# medibox.net
KiCad netlist of a schematic drawn in Altium Designer
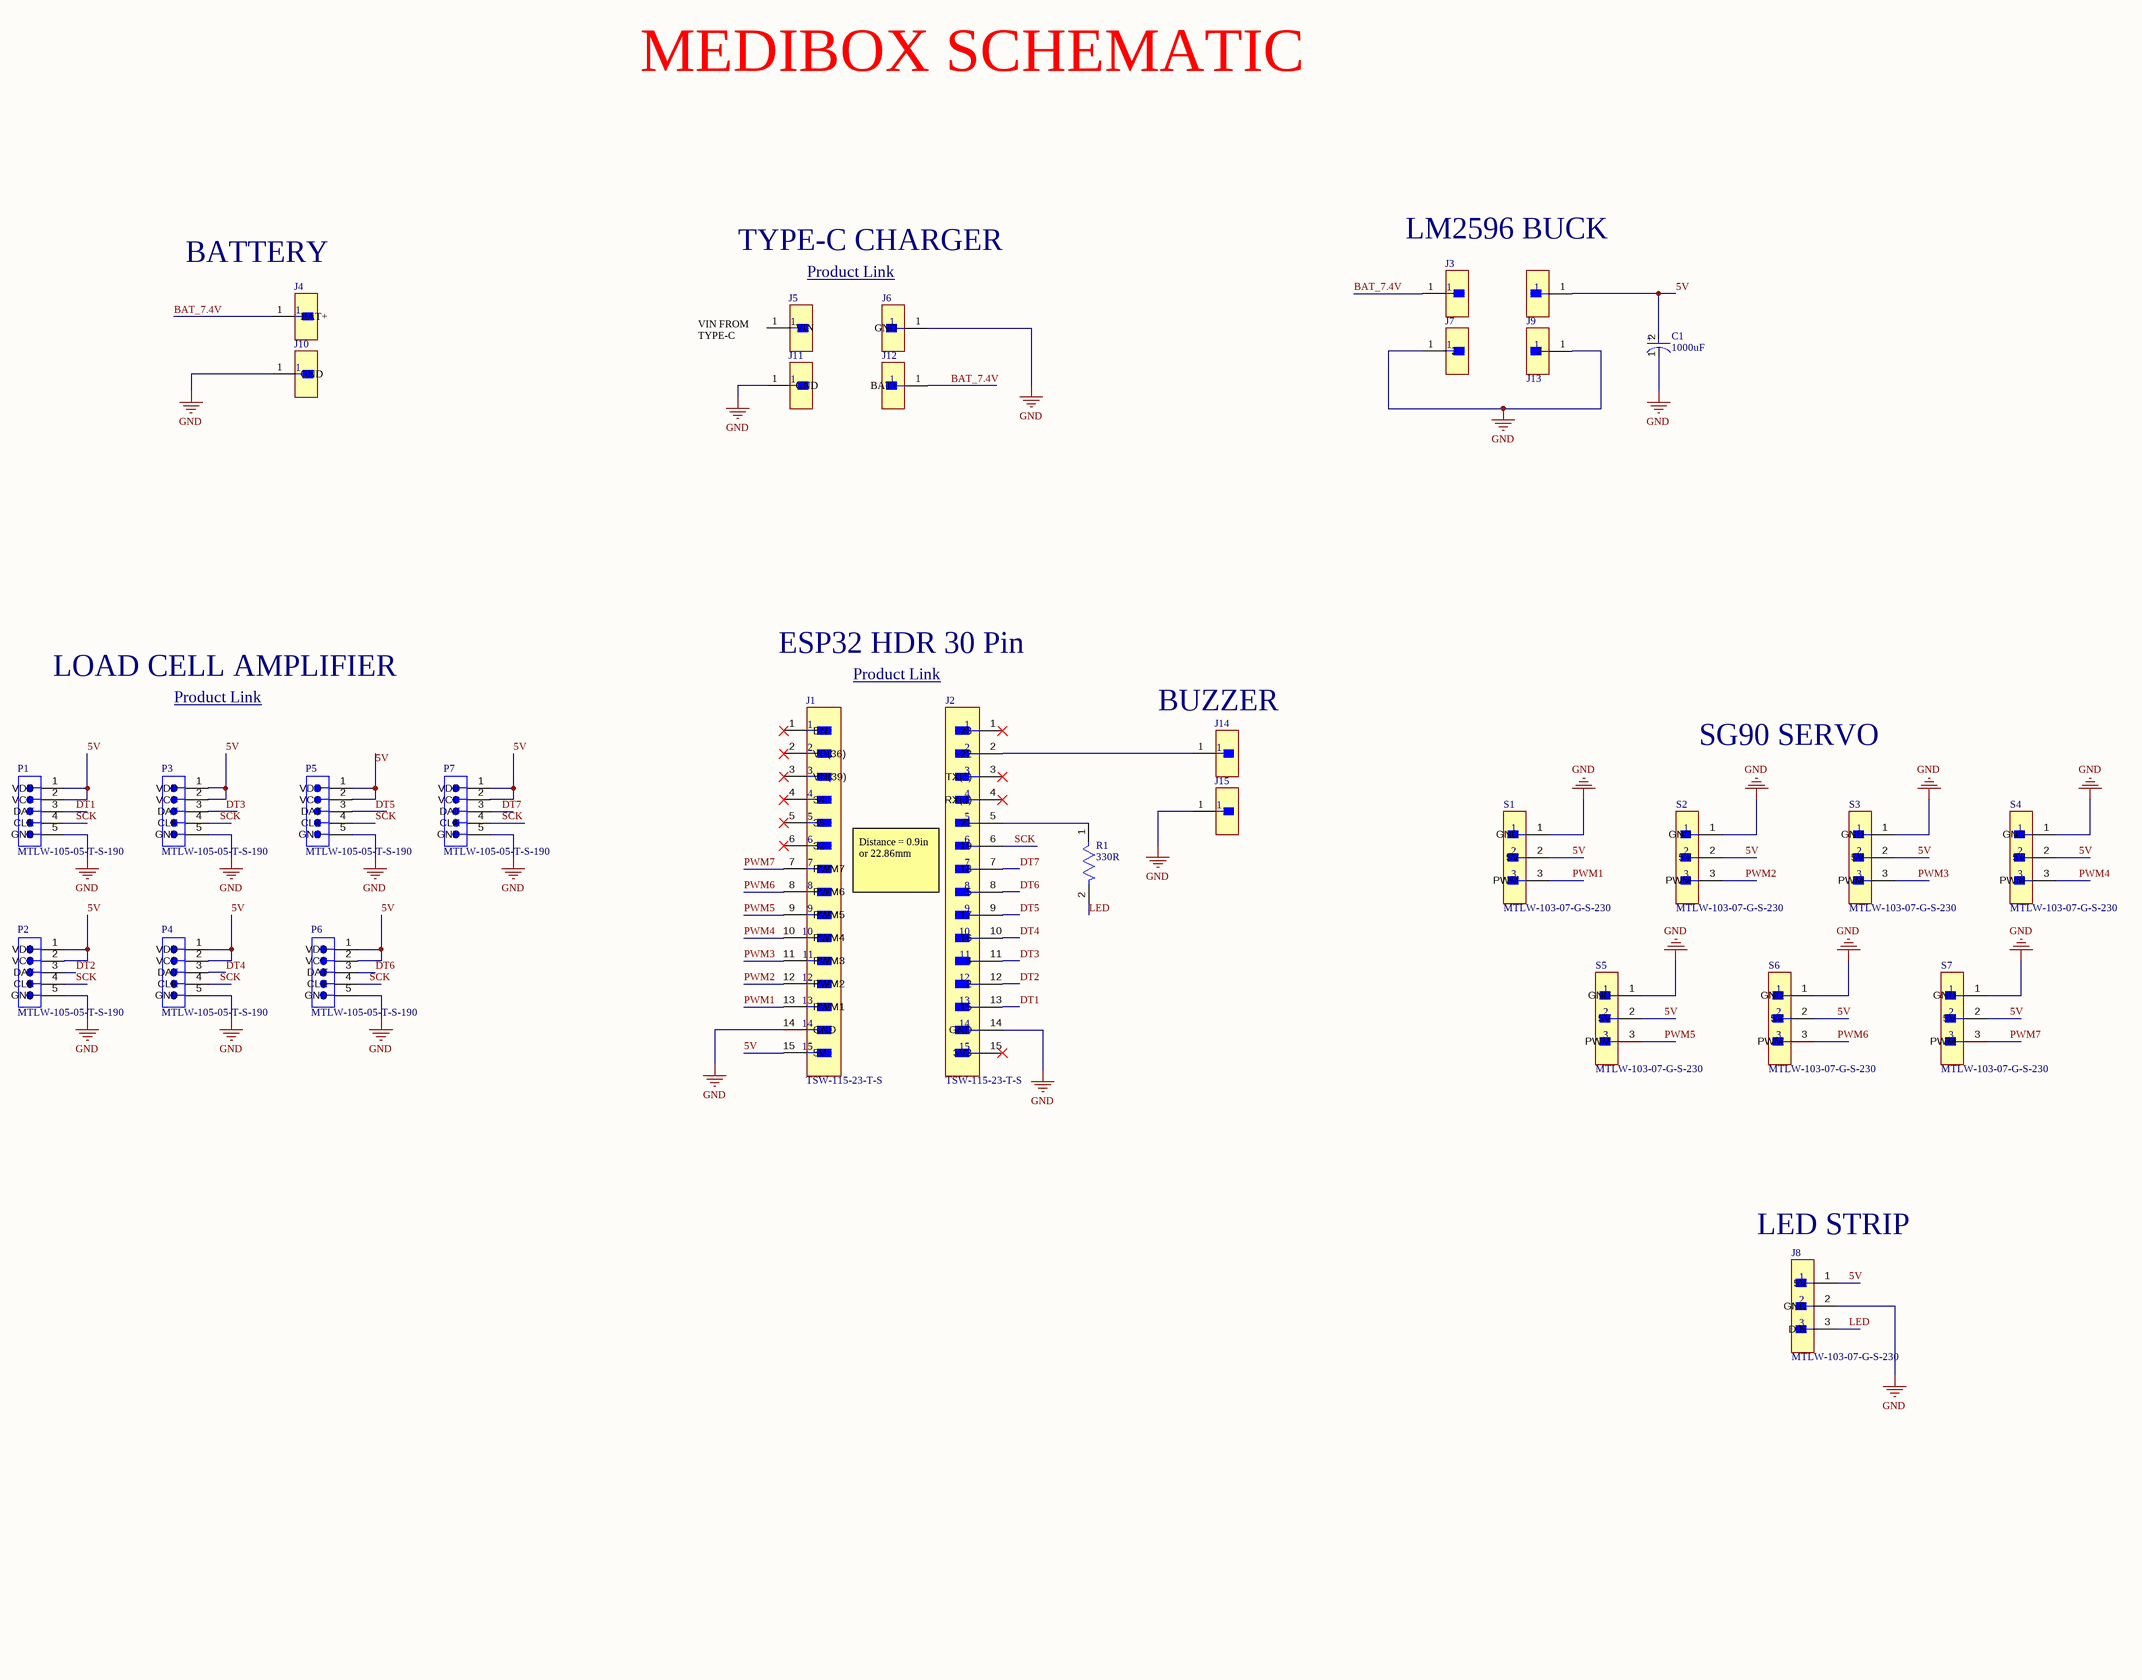
[diagram p0: medibox.SchDoc]

(export (version "E")
  (design (tool "Eeschema 10.0.6"))
  (components
    (comp (ref "C1")
      (value "1000uF")
      (footprint "FP-RAD-TH-D_10_0_5-L_25_2-MFG")
      (description "EEUFC1C102B Aluminum Electrolytic Capacitors (Radial Lead Type) AEC-Q200 Qualified 1000uF ±20% 16V")
      (fields (field (name "TOLERANCE") "20%"))
      (libsource (lib "Altium Content Vault") (part "a00bbbee19879c290e62620ae7e47b1"))
    )
    (comp (ref "J1")
      (value "TSW-115-23-T-S")
      (footprint "FP-TSW-115-23-T-S-MFG")
      (description "CONN HEADER VERT 15POS 2.54MM")
      (libsource (lib "Altium Content Vault") (part "9e54aee09c46527fb07af492d4d8164"))
    )
    (comp (ref "J2")
      (value "TSW-115-23-T-S")
      (footprint "FP-TSW-115-23-T-S-MFG")
      (description "CONN HEADER VERT 15POS 2.54MM")
      (libsource (lib "") (part "9e54aee09c46527fb07af492d4d8164_1"))
    )
    (comp (ref "J3")
      (value "68000-401HLF")
      (footprint "FP-68000-401HLF-MFG")
      (description "68000-401HLF Conn Unshrouded Header HDR 1 POS Solder ST Top Entry Thru-Hole BergStik® Bulk")
      (libsource (lib "") (part "dd45045ce8184df9e99e12baf3f412c_2"))
    )
    (comp (ref "J4")
      (value "68000-401HLF")
      (footprint "FP-68000-401HLF-MFG")
      (description "68000-401HLF Conn Unshrouded Header HDR 1 POS Solder ST Top Entry Thru-Hole BergStik® Bulk")
      (libsource (lib "") (part "dd45045ce8184df9e99e12baf3f412c_3"))
    )
    (comp (ref "J5")
      (value "68000-401HLF")
      (footprint "FP-68000-401HLF-MFG")
      (description "68000-401HLF Conn Unshrouded Header HDR 1 POS Solder ST Top Entry Thru-Hole BergStik® Bulk")
      (libsource (lib "") (part "dd45045ce8184df9e99e12baf3f412c_6"))
    )
    (comp (ref "J6")
      (value "68000-401HLF")
      (footprint "FP-68000-401HLF-MFG")
      (description "68000-401HLF Conn Unshrouded Header HDR 1 POS Solder ST Top Entry Thru-Hole BergStik® Bulk")
      (libsource (lib "") (part "dd45045ce8184df9e99e12baf3f412c_1"))
    )
    (comp (ref "J7")
      (value "68000-401HLF")
      (footprint "FP-68000-401HLF-MFG")
      (description "68000-401HLF Conn Unshrouded Header HDR 1 POS Solder ST Top Entry Thru-Hole BergStik® Bulk")
      (libsource (lib "") (part "dd45045ce8184df9e99e12baf3f412c_5"))
    )
    (comp (ref "J8")
      (value "MTLW-103-07-G-S-230")
      (footprint "FP-MTLW-103-07-G-S-230-MFG")
      (description "CONN HEADER VERT 3POS 2.54MM")
      (libsource (lib "Altium Content Vault") (part "0d3f023dd272f625e17a2be33dea85f"))
    )
    (comp (ref "J9")
      (value "68000-401HLF")
      (footprint "FP-68000-401HLF-MFG")
      (description "68000-401HLF Conn Unshrouded Header HDR 1 POS Solder ST Top Entry Thru-Hole BergStik® Bulk")
      (libsource (lib "") (part "dd45045ce8184df9e99e12baf3f412c_7"))
    )
    (comp (ref "J10")
      (value "68000-401HLF")
      (footprint "FP-68000-401HLF-MFG")
      (description "68000-401HLF Conn Unshrouded Header HDR 1 POS Solder ST Top Entry Thru-Hole BergStik® Bulk")
      (libsource (lib "Altium Content Vault") (part "dd45045ce8184df9e99e12baf3f412c"))
    )
    (comp (ref "J11")
      (value "68000-401HLF")
      (footprint "FP-68000-401HLF-MFG")
      (description "68000-401HLF Conn Unshrouded Header HDR 1 POS Solder ST Top Entry Thru-Hole BergStik® Bulk")
      (libsource (lib "Altium Content Vault") (part "dd45045ce8184df9e99e12baf3f412c"))
    )
    (comp (ref "J12")
      (value "68000-401HLF")
      (footprint "FP-68000-401HLF-MFG")
      (description "68000-401HLF Conn Unshrouded Header HDR 1 POS Solder ST Top Entry Thru-Hole BergStik® Bulk")
      (libsource (lib "") (part "dd45045ce8184df9e99e12baf3f412c_1"))
    )
    (comp (ref "J13")
      (value "68000-401HLF")
      (footprint "FP-68000-401HLF-MFG")
      (description "68000-401HLF Conn Unshrouded Header HDR 1 POS Solder ST Top Entry Thru-Hole BergStik® Bulk")
      (libsource (lib "") (part "dd45045ce8184df9e99e12baf3f412c_1"))
    )
    (comp (ref "J14")
      (value "68000-401HLF")
      (footprint "FP-68000-401HLF-MFG")
      (description "68000-401HLF Conn Unshrouded Header HDR 1 POS Solder ST Top Entry Thru-Hole BergStik® Bulk")
      (libsource (lib "") (part "dd45045ce8184df9e99e12baf3f412c_2"))
    )
    (comp (ref "J15")
      (value "68000-401HLF")
      (footprint "FP-68000-401HLF-MFG")
      (description "68000-401HLF Conn Unshrouded Header HDR 1 POS Solder ST Top Entry Thru-Hole BergStik® Bulk")
      (libsource (lib "") (part "dd45045ce8184df9e99e12baf3f412c_4"))
    )
    (comp (ref "P1")
      (value "MTLW-105-05-T-S-190")
      (footprint "SMTC-MTLW-105-05-X-S-190")
      (fields (field (name "MANUFACTURER") "Samtec"))
      (libsource (lib "Altium Content Vault") (part "SMTC-MTLW-105-05-X-S-190"))
    )
    (comp (ref "P2")
      (value "MTLW-105-05-T-S-190")
      (footprint "SMTC-MTLW-105-05-X-S-190")
      (fields (field (name "MANUFACTURER") "Samtec"))
      (libsource (lib "Altium Content Vault") (part "SMTC-MTLW-105-05-X-S-190"))
    )
    (comp (ref "P3")
      (value "MTLW-105-05-T-S-190")
      (footprint "SMTC-MTLW-105-05-X-S-190")
      (fields (field (name "MANUFACTURER") "Samtec"))
      (libsource (lib "Altium Content Vault") (part "SMTC-MTLW-105-05-X-S-190"))
    )
    (comp (ref "P4")
      (value "MTLW-105-05-T-S-190")
      (footprint "SMTC-MTLW-105-05-X-S-190")
      (fields (field (name "MANUFACTURER") "Samtec"))
      (libsource (lib "Altium Content Vault") (part "SMTC-MTLW-105-05-X-S-190"))
    )
    (comp (ref "P5")
      (value "MTLW-105-05-T-S-190")
      (footprint "SMTC-MTLW-105-05-X-S-190")
      (fields (field (name "MANUFACTURER") "Samtec"))
      (libsource (lib "Altium Content Vault") (part "SMTC-MTLW-105-05-X-S-190"))
    )
    (comp (ref "P6")
      (value "MTLW-105-05-T-S-190")
      (footprint "SMTC-MTLW-105-05-X-S-190")
      (fields (field (name "MANUFACTURER") "Samtec"))
      (libsource (lib "Altium Content Vault") (part "SMTC-MTLW-105-05-X-S-190"))
    )
    (comp (ref "P7")
      (value "MTLW-105-05-T-S-190")
      (footprint "SMTC-MTLW-105-05-X-S-190")
      (fields (field (name "MANUFACTURER") "Samtec"))
      (libsource (lib "Altium Content Vault") (part "SMTC-MTLW-105-05-X-S-190"))
    )
    (comp (ref "R1")
      (value "330R")
      (footprint "FP-RMCF0805-IPC_C")
      (description "RMCF0805FT330R 330Ω ±1% 0.125W 0805 Thick Film Chip Resistor AEC-Q200 compliant")
      (fields (field (name "TOLERANCE") "1%"))
      (libsource (lib "Altium Content Vault") (part "1029c3af85768c4190bb7ad29bc67b5"))
    )
    (comp (ref "S1")
      (value "MTLW-103-07-G-S-230")
      (footprint "FP-MTLW-103-07-G-S-230-MFG")
      (description "CONN HEADER VERT 3POS 2.54MM")
      (libsource (lib "Altium Content Vault") (part "0d3f023dd272f625e17a2be33dea85f"))
    )
    (comp (ref "S2")
      (value "MTLW-103-07-G-S-230")
      (footprint "FP-MTLW-103-07-G-S-230-MFG")
      (description "CONN HEADER VERT 3POS 2.54MM")
      (libsource (lib "Altium Content Vault") (part "0d3f023dd272f625e17a2be33dea85f"))
    )
    (comp (ref "S3")
      (value "MTLW-103-07-G-S-230")
      (footprint "FP-MTLW-103-07-G-S-230-MFG")
      (description "CONN HEADER VERT 3POS 2.54MM")
      (libsource (lib "Altium Content Vault") (part "0d3f023dd272f625e17a2be33dea85f"))
    )
    (comp (ref "S4")
      (value "MTLW-103-07-G-S-230")
      (footprint "FP-MTLW-103-07-G-S-230-MFG")
      (description "CONN HEADER VERT 3POS 2.54MM")
      (libsource (lib "Altium Content Vault") (part "0d3f023dd272f625e17a2be33dea85f"))
    )
    (comp (ref "S5")
      (value "MTLW-103-07-G-S-230")
      (footprint "FP-MTLW-103-07-G-S-230-MFG")
      (description "CONN HEADER VERT 3POS 2.54MM")
      (libsource (lib "Altium Content Vault") (part "0d3f023dd272f625e17a2be33dea85f"))
    )
    (comp (ref "S6")
      (value "MTLW-103-07-G-S-230")
      (footprint "FP-MTLW-103-07-G-S-230-MFG")
      (description "CONN HEADER VERT 3POS 2.54MM")
      (libsource (lib "Altium Content Vault") (part "0d3f023dd272f625e17a2be33dea85f"))
    )
    (comp (ref "S7")
      (value "MTLW-103-07-G-S-230")
      (footprint "FP-MTLW-103-07-G-S-230-MFG")
      (description "CONN HEADER VERT 3POS 2.54MM")
      (libsource (lib "Altium Content Vault") (part "0d3f023dd272f625e17a2be33dea85f"))
    )
  )
  (nets
    (net (code "1") (name "/5V") (class "Default")
      (node (ref "C1") (pin "2") (pinfunction "A_2") (pintype "passive"))
      (node (ref "J1") (pin "15") (pinfunction "5V_15") (pintype "passive"))
      (node (ref "J8") (pin "1") (pinfunction "5V_1") (pintype "passive"))
      (node (ref "J9") (pin "1") (pinfunction "1_1") (pintype "passive"))
      (node (ref "P1") (pin "1") (pinfunction "VDD_1") (pintype "passive"))
      (node (ref "P1") (pin "2") (pinfunction "VCC_2") (pintype "passive"))
      (node (ref "P2") (pin "1") (pinfunction "VDD_1") (pintype "passive"))
      (node (ref "P2") (pin "2") (pinfunction "VCC_2") (pintype "passive"))
      (node (ref "P3") (pin "1") (pinfunction "VDD_1") (pintype "passive"))
      (node (ref "P3") (pin "2") (pinfunction "VCC_2") (pintype "passive"))
      (node (ref "P4") (pin "1") (pinfunction "VDD_1") (pintype "passive"))
      (node (ref "P4") (pin "2") (pinfunction "VCC_2") (pintype "passive"))
      (node (ref "P5") (pin "1") (pinfunction "VDD_1") (pintype "passive"))
      (node (ref "P5") (pin "2") (pinfunction "VCC_2") (pintype "passive"))
      (node (ref "P6") (pin "1") (pinfunction "VDD_1") (pintype "passive"))
      (node (ref "P6") (pin "2") (pinfunction "VCC_2") (pintype "passive"))
      (node (ref "P7") (pin "1") (pinfunction "VDD_1") (pintype "passive"))
      (node (ref "P7") (pin "2") (pinfunction "VCC_2") (pintype "passive"))
      (node (ref "S1") (pin "2") (pinfunction "GND_2") (pintype "passive"))
      (node (ref "S2") (pin "2") (pinfunction "GND_2") (pintype "passive"))
      (node (ref "S3") (pin "2") (pinfunction "GND_2") (pintype "passive"))
      (node (ref "S4") (pin "2") (pinfunction "GND_2") (pintype "passive"))
      (node (ref "S5") (pin "2") (pinfunction "GND_2") (pintype "passive"))
      (node (ref "S6") (pin "2") (pinfunction "GND_2") (pintype "passive"))
      (node (ref "S7") (pin "2") (pinfunction "GND_2") (pintype "passive"))
    )
    (net (code "2") (name "/BAT_7.4V") (class "Default")
      (node (ref "J12") (pin "1") (pinfunction "GND_1") (pintype "passive"))
      (node (ref "J3") (pin "1") (pinfunction "1_1") (pintype "passive"))
      (node (ref "J4") (pin "1") (pinfunction "BAT+_1") (pintype "passive"))
    )
    (net (code "3") (name "/DT1") (class "Default")
      (node (ref "J2") (pin "13") (pinfunction "15_13") (pintype "passive"))
      (node (ref "P1") (pin "3") (pinfunction "DAT_3") (pintype "passive"))
    )
    (net (code "4") (name "/DT2") (class "Default")
      (node (ref "J2") (pin "12") (pinfunction "2_12") (pintype "passive"))
      (node (ref "P2") (pin "3") (pinfunction "DAT_3") (pintype "passive"))
    )
    (net (code "5") (name "/DT3") (class "Default")
      (node (ref "J2") (pin "11") (pinfunction "4_11") (pintype "passive"))
      (node (ref "P3") (pin "3") (pinfunction "DAT_3") (pintype "passive"))
    )
    (net (code "6") (name "/DT4") (class "Default")
      (node (ref "J2") (pin "10") (pinfunction "16_10") (pintype "passive"))
      (node (ref "P4") (pin "3") (pinfunction "DAT_3") (pintype "passive"))
    )
    (net (code "7") (name "/DT5") (class "Default")
      (node (ref "J2") (pin "9") (pinfunction "17_9") (pintype "passive"))
      (node (ref "P5") (pin "3") (pinfunction "DAT_3") (pintype "passive"))
    )
    (net (code "8") (name "/DT6") (class "Default")
      (node (ref "J2") (pin "8") (pinfunction "5_8") (pintype "passive"))
      (node (ref "P6") (pin "3") (pinfunction "DAT_3") (pintype "passive"))
    )
    (net (code "9") (name "/DT7") (class "Default")
      (node (ref "J2") (pin "7") (pinfunction "18_7") (pintype "passive"))
      (node (ref "P7") (pin "3") (pinfunction "DAT_3") (pintype "passive"))
    )
    (net (code "10") (name "/LED") (class "Default")
      (node (ref "J8") (pin "3") (pinfunction "DIN_3") (pintype "passive"))
      (node (ref "R1") (pin "2") (pinfunction "2_2") (pintype "passive"))
    )
    (net (code "11") (name "/PWM1") (class "Default")
      (node (ref "J1") (pin "13") (pinfunction "PWM1_13") (pintype "passive"))
      (node (ref "S1") (pin "3") (pinfunction "DIN_3") (pintype "passive"))
    )
    (net (code "12") (name "/PWM2") (class "Default")
      (node (ref "J1") (pin "12") (pinfunction "PWM2_12") (pintype "passive"))
      (node (ref "S2") (pin "3") (pinfunction "DIN_3") (pintype "passive"))
    )
    (net (code "13") (name "/PWM3") (class "Default")
      (node (ref "J1") (pin "11") (pinfunction "PWM3_11") (pintype "passive"))
      (node (ref "S3") (pin "3") (pinfunction "DIN_3") (pintype "passive"))
    )
    (net (code "14") (name "/PWM4") (class "Default")
      (node (ref "J1") (pin "10") (pinfunction "PWM4_10") (pintype "passive"))
      (node (ref "S4") (pin "3") (pinfunction "DIN_3") (pintype "passive"))
    )
    (net (code "15") (name "/PWM5") (class "Default")
      (node (ref "J1") (pin "9") (pinfunction "PWM5_9") (pintype "passive"))
      (node (ref "S5") (pin "3") (pinfunction "DIN_3") (pintype "passive"))
    )
    (net (code "16") (name "/PWM6") (class "Default")
      (node (ref "J1") (pin "8") (pinfunction "PWM6_8") (pintype "passive"))
      (node (ref "S6") (pin "3") (pinfunction "DIN_3") (pintype "passive"))
    )
    (net (code "17") (name "/PWM7") (class "Default")
      (node (ref "J1") (pin "7") (pinfunction "PWM7_7") (pintype "passive"))
      (node (ref "S7") (pin "3") (pinfunction "DIN_3") (pintype "passive"))
    )
    (net (code "18") (name "/SCK") (class "Default")
      (node (ref "J2") (pin "6") (pinfunction "19_6") (pintype "passive"))
      (node (ref "P1") (pin "4") (pinfunction "CLK_4") (pintype "passive"))
      (node (ref "P2") (pin "4") (pinfunction "CLK_4") (pintype "passive"))
      (node (ref "P3") (pin "4") (pinfunction "CLK_4") (pintype "passive"))
      (node (ref "P4") (pin "4") (pinfunction "CLK_4") (pintype "passive"))
      (node (ref "P5") (pin "4") (pinfunction "CLK_4") (pintype "passive"))
      (node (ref "P6") (pin "4") (pinfunction "CLK_4") (pintype "passive"))
      (node (ref "P7") (pin "4") (pinfunction "CLK_4") (pintype "passive"))
    )
    (net (code "19") (name "GND") (class "Default")
      (node (ref "C1") (pin "1") (pinfunction "C_1") (pintype "passive"))
      (node (ref "J1") (pin "14") (pinfunction "GND_14") (pintype "passive"))
      (node (ref "J10") (pin "1") (pinfunction "GND_1") (pintype "passive"))
      (node (ref "J11") (pin "1") (pinfunction "GND_1") (pintype "passive"))
      (node (ref "J13") (pin "1") (pinfunction "GND_1") (pintype "passive"))
      (node (ref "J15") (pin "1") (pinfunction "2_1") (pintype "passive"))
      (node (ref "J2") (pin "14") (pinfunction "GND_14") (pintype "passive"))
      (node (ref "J6") (pin "1") (pinfunction "GND_1") (pintype "passive"))
      (node (ref "J7") (pin "1") (pinfunction "2_1") (pintype "passive"))
      (node (ref "J8") (pin "2") (pinfunction "GND_2") (pintype "passive"))
      (node (ref "P1") (pin "5") (pinfunction "GND_5") (pintype "passive"))
      (node (ref "P2") (pin "5") (pinfunction "GND_5") (pintype "passive"))
      (node (ref "P3") (pin "5") (pinfunction "GND_5") (pintype "passive"))
      (node (ref "P4") (pin "5") (pinfunction "GND_5") (pintype "passive"))
      (node (ref "P5") (pin "5") (pinfunction "GND_5") (pintype "passive"))
      (node (ref "P6") (pin "5") (pinfunction "GND_5") (pintype "passive"))
      (node (ref "P7") (pin "5") (pinfunction "GND_5") (pintype "passive"))
      (node (ref "S1") (pin "1") (pinfunction "5V_1") (pintype "passive"))
      (node (ref "S2") (pin "1") (pinfunction "5V_1") (pintype "passive"))
      (node (ref "S3") (pin "1") (pinfunction "5V_1") (pintype "passive"))
      (node (ref "S4") (pin "1") (pinfunction "5V_1") (pintype "passive"))
      (node (ref "S5") (pin "1") (pinfunction "5V_1") (pintype "passive"))
      (node (ref "S6") (pin "1") (pinfunction "5V_1") (pintype "passive"))
      (node (ref "S7") (pin "1") (pinfunction "5V_1") (pintype "passive"))
    )
    (net (code "20") (name "Net-(J2-21)") (class "Default")
      (node (ref "J2") (pin "5") (pinfunction "21_5") (pintype "passive"))
      (node (ref "R1") (pin "1") (pinfunction "1_1") (pintype "passive"))
    )
    (net (code "21") (name "Net-(J2-22)") (class "Default")
      (node (ref "J14") (pin "1") (pinfunction "1_1") (pintype "passive"))
      (node (ref "J2") (pin "2") (pinfunction "22_2") (pintype "passive"))
    )
    (net (code "22") (name "unconnected-(J1-32-Pad6)") (class "Default")
      (node (ref "J1") (pin "6") (pinfunction "32_6") (pintype "passive+no_connect"))
    )
    (net (code "23") (name "unconnected-(J1-34-Pad4)") (class "Default")
      (node (ref "J1") (pin "4") (pinfunction "34_4") (pintype "passive+no_connect"))
    )
    (net (code "24") (name "unconnected-(J1-35-Pad5)") (class "Default")
      (node (ref "J1") (pin "5") (pinfunction "35_5") (pintype "passive+no_connect"))
    )
    (net (code "25") (name "unconnected-(J1-EN-Pad1)") (class "Default")
      (node (ref "J1") (pin "1") (pinfunction "EN_1") (pintype "passive+no_connect"))
    )
    (net (code "26") (name "unconnected-(J1-VN(39)-Pad3)") (class "Default")
      (node (ref "J1") (pin "3") (pinfunction "VN(39)_3") (pintype "passive+no_connect"))
    )
    (net (code "27") (name "unconnected-(J1-VP(36)-Pad2)") (class "Default")
      (node (ref "J1") (pin "2") (pinfunction "VP(36)_2") (pintype "passive+no_connect"))
    )
    (net (code "28") (name "unconnected-(J2-3V3-Pad15)") (class "Default")
      (node (ref "J2") (pin "15") (pinfunction "3V3_15") (pintype "passive+no_connect"))
    )
    (net (code "29") (name "unconnected-(J2-23-Pad1)") (class "Default")
      (node (ref "J2") (pin "1") (pinfunction "23_1") (pintype "passive+no_connect"))
    )
    (net (code "30") (name "unconnected-(J2-RX(3)-Pad4)") (class "Default")
      (node (ref "J2") (pin "4") (pinfunction "RX(3)_4") (pintype "passive+no_connect"))
    )
    (net (code "31") (name "unconnected-(J2-TX(1)-Pad3)") (class "Default")
      (node (ref "J2") (pin "3") (pinfunction "TX(1)_3") (pintype "passive+no_connect"))
    )
    (net (code "32") (name "unconnected-(J5-VIN-Pad1)") (class "Default")
      (node (ref "J5") (pin "1") (pinfunction "VIN_1") (pintype "passive"))
    )
  )
)
